# RTCE.net
KiCad netlist of a schematic drawn in Altium Designer
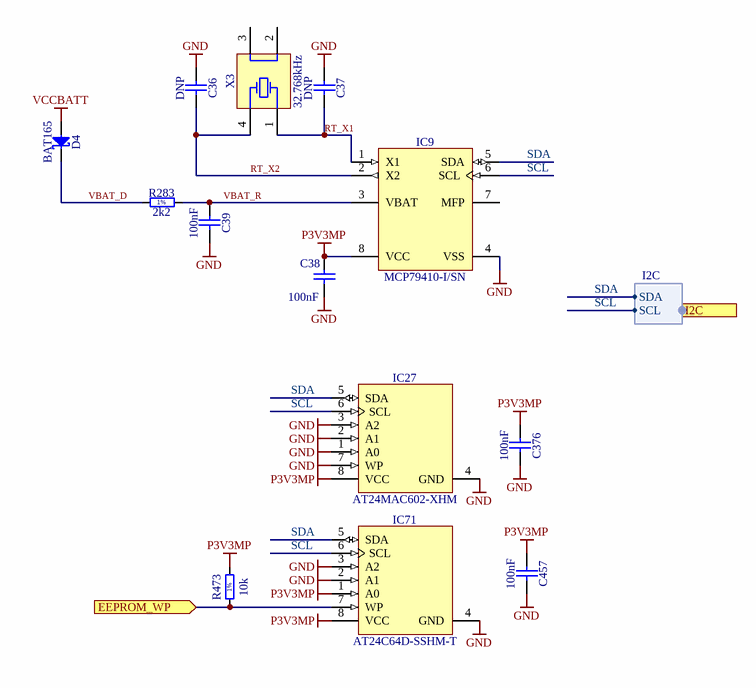
[diagram p0: RTCE.SchDoc]

(export (version "E")
  (design (tool "Eeschema 10.0.6"))
  (components
    (comp (ref "C36")
      (value "DNP")
      (footprint "CAPC1005X55N")
      (description "Non-polarised capacitor")
      (fields
        (field (name "PART NUMBER") "CC0402_15PF_50V_5%_NP0")
        (field (name "VOLTAGE") "50V")
        (field (name "AUTHOR") "CERN DEM JLC")
      )
      (libsource (lib "Capacitors") (part "Capacitor - non polarized"))
    )
    (comp (ref "C37")
      (value "DNP")
      (footprint "CAPC1005X55N")
      (description "Non-polarised capacitor")
      (fields
        (field (name "PART NUMBER") "CC0402_15PF_50V_5%_NP0")
        (field (name "VOLTAGE") "50V")
        (field (name "AUTHOR") "CERN DEM JLC")
      )
      (libsource (lib "Capacitors") (part "Capacitor - non polarized"))
    )
    (comp (ref "C38")
      (value "100nF")
      (footprint "CAPC0603X33N")
      (description "Non-polarised capacitor")
      (fields
        (field (name "PART NUMBER") "CC0201_100NF_6.3V_10%_X5R")
        (field (name "VOLTAGE") "6.3V")
        (field (name "AUTHOR") "CERN DEM JLC")
      )
      (libsource (lib "Capacitors") (part "Capacitor - non polarized"))
    )
    (comp (ref "C39")
      (value "100nF")
      (footprint "CAPC0603X33N")
      (description "Non-polarised capacitor")
      (fields
        (field (name "PART NUMBER") "CC0201_100NF_6.3V_10%_X5R")
        (field (name "VOLTAGE") "6.3V")
        (field (name "AUTHOR") "CERN DEM JLC")
      )
      (libsource (lib "Capacitors") (part "Capacitor - non polarized"))
    )
    (comp (ref "C376")
      (value "100nF")
      (footprint "CAPC0603X33N")
      (description "Non-polarised capacitor")
      (fields
        (field (name "PART NUMBER") "CC0201_100NF_6.3V_10%_X5R")
        (field (name "VOLTAGE") "6.3V")
        (field (name "AUTHOR") "CERN DEM JLC")
      )
      (libsource (lib "Capacitors") (part "Capacitor - non polarized"))
    )
    (comp (ref "C457")
      (value "100nF")
      (footprint "CAPC0603X33N")
      (description "Non-polarised capacitor")
      (fields
        (field (name "PART NUMBER") "CC0201_100NF_6.3V_10%_X5R")
        (field (name "VOLTAGE") "6.3V")
        (field (name "AUTHOR") "CERN DEM JLC")
      )
      (libsource (lib "Capacitors") (part "Capacitor - non polarized"))
    )
    (comp (ref "D4")
      (value "BAT165")
      (footprint "SOD2512X110N")
      (description "Schottky Diode")
      (fields
        (field (name "VOLTAGE") "40V")
        (field (name "POWER") "750mA")
        (field (name "AUTHOR") "CERN DEM JLC")
      )
      (libsource (lib "ICs And Semiconductors") (part "Diode Schottky"))
    )
    (comp (ref "IC9")
      (value "MCP79410-I/SN")
      (footprint "SOIC127P600X175-8N")
      (description "I2C Real-Time Clock/Calendar with EEPROM, SRAM, Unique ID and Battery Switchover")
      (fields (field (name "MANUFACTURER") "MICROCHIP TECHNOLOGY") (field (name "AUTHOR") "CERN DEM JMW"))
      (libsource (lib "ICs And Semiconductors") (part "MCP79410"))
    )
    (comp (ref "IC27")
      (value "AT24MAC602-XHM")
      (footprint "SOP65P640X120-8N")
      (description "1.7V to 5.5V, I2C-Compatible (2-wire) 2-Kbit (256 x 8) Serial EEPROM")
      (fields (field (name "MANUFACTURER") "ATMEL") (field (name "AUTHOR") "CERN DEM MR"))
      (libsource (lib "ICs And Semiconductors") (part "AT24MAC602-XHM"))
    )
    (comp (ref "IC71")
      (value "AT24C64D-SSHM-T")
      (footprint "SOIC127P600X175-8N")
      (description "64K (8192 x 8), I2C-Compatible (2-Wire) Serial EEPROM")
      (fields (field (name "MANUFACTURER") "ATMEL") (field (name "AUTHOR") "CERN DEM JLC"))
      (libsource (lib "ICs And Semiconductors") (part "AT24C64D-SSH"))
    )
    (comp (ref "R283")
      (value "2k2")
      (footprint "RESC1005X40N")
      (description "Resistor - 1%")
      (fields
        (field (name "PART NUMBER") "R0402_2K2_1%_0.0625W_100PPM")
        (field (name "POWER") "0.0625W")
        (field (name "AUTHOR") "CERN DEM JLC")
      )
      (libsource (lib "Resistors") (part "Resistor - 1%"))
    )
    (comp (ref "R473")
      (value "10k")
      (footprint "RESC1005X40N")
      (description "Resistor - 1%")
      (fields
        (field (name "MANUFACTURER PART NUMBER") "R0402_10K_1%_0.0625W_100PPM")
        (field (name "MANUFACTURER") "GENERIC")
        (field (name "AUTHOR") "CERN DEM JLC")
      )
      (libsource (lib "Resistors") (part "Resistor - 1%"))
    )
    (comp (ref "X3")
      (value "32.768kHz")
      (footprint "XTAL_ABRACON_ABS25")
      (description "Crystal 4 pins 1=XTAL Control 2 And 3=NC 4=XTAL")
      (fields
        (field (name "PART NUMBER") "XTAL_32.768KHZ_ABRACON_ABS25-32.768KHZ-T")
        (field (name "MANUFACTURER") "ABRACON")
        (field (name "AUTHOR") "CERN DEM JMW")
      )
      (libsource (lib "ICs And Semiconductors") (part "Quartz Crystal 1X 2-3NC 4X"))
    )
  )
  (nets
    (net (code "2") (name "/EEPROM_WP") (class "Default")
      (node (ref "IC71") (pin "7") (pinfunction "WP_7") (pintype "input"))
      (node (ref "R473") (pin "1") (pinfunction "1_1") (pintype "passive"))
    )
    (net (code "3") (name "/RT_X1") (class "Default")
      (node (ref "C37") (pin "2") (pinfunction "2_2") (pintype "passive"))
      (node (ref "IC9") (pin "1") (pinfunction "X1_1") (pintype "input"))
      (node (ref "X3") (pin "1") (pinfunction "X_1") (pintype "passive"))
    )
    (net (code "4") (name "/RT_X2") (class "Default")
      (node (ref "C36") (pin "2") (pinfunction "2_2") (pintype "passive"))
      (node (ref "IC9") (pin "2") (pinfunction "X2_2") (pintype "output"))
      (node (ref "X3") (pin "4") (pinfunction "X_4") (pintype "passive"))
    )
    (net (code "5") (name "/SCL") (class "Default")
      (node (ref "IC27") (pin "6") (pinfunction "SCL_6") (pintype "input"))
      (node (ref "IC71") (pin "6") (pinfunction "SCL_6") (pintype "input"))
      (node (ref "IC9") (pin "6") (pinfunction "SCL_6") (pintype "input"))
    )
    (net (code "6") (name "/SDA") (class "Default")
      (node (ref "IC27") (pin "5") (pinfunction "SDA_5") (pintype "bidirectional"))
      (node (ref "IC71") (pin "5") (pinfunction "SDA_5") (pintype "bidirectional"))
      (node (ref "IC9") (pin "5") (pinfunction "SDA_5") (pintype "bidirectional"))
    )
    (net (code "7") (name "/VBAT_D") (class "Default")
      (node (ref "D4") (pin "1") (pinfunction "C_1") (pintype "passive"))
      (node (ref "R283") (pin "1") (pinfunction "1_1") (pintype "passive"))
    )
    (net (code "8") (name "/VBAT_R") (class "Default")
      (node (ref "C39") (pin "1") (pinfunction "1_1") (pintype "passive"))
      (node (ref "IC9") (pin "3") (pinfunction "VBAT_3") (pintype "power_in"))
      (node (ref "R283") (pin "2") (pinfunction "2_2") (pintype "passive"))
    )
    (net (code "10") (name "GND") (class "Default")
      (node (ref "C36") (pin "1") (pinfunction "1_1") (pintype "passive"))
      (node (ref "C37") (pin "1") (pinfunction "1_1") (pintype "passive"))
      (node (ref "C376") (pin "2") (pinfunction "2_2") (pintype "passive"))
      (node (ref "C38") (pin "2") (pinfunction "2_2") (pintype "passive"))
      (node (ref "C39") (pin "2") (pinfunction "2_2") (pintype "passive"))
      (node (ref "C457") (pin "2") (pinfunction "2_2") (pintype "passive"))
      (node (ref "IC27") (pin "1") (pinfunction "A0_1") (pintype "input"))
      (node (ref "IC27") (pin "2") (pinfunction "A1_2") (pintype "input"))
      (node (ref "IC27") (pin "3") (pinfunction "A2_3") (pintype "input"))
      (node (ref "IC27") (pin "4") (pinfunction "GND_4") (pintype "power_in"))
      (node (ref "IC27") (pin "7") (pinfunction "WP_7") (pintype "input"))
      (node (ref "IC71") (pin "2") (pinfunction "A1_2") (pintype "input"))
      (node (ref "IC71") (pin "3") (pinfunction "A2_3") (pintype "input"))
      (node (ref "IC71") (pin "4") (pinfunction "GND_4") (pintype "power_in"))
      (node (ref "IC9") (pin "4") (pinfunction "VSS_4") (pintype "power_in"))
    )
    (net (code "11") (name "P3V3MP") (class "Default")
      (node (ref "C376") (pin "1") (pinfunction "1_1") (pintype "passive"))
      (node (ref "C38") (pin "1") (pinfunction "1_1") (pintype "passive"))
      (node (ref "C457") (pin "1") (pinfunction "1_1") (pintype "passive"))
      (node (ref "IC27") (pin "8") (pinfunction "VCC_8") (pintype "power_in"))
      (node (ref "IC71") (pin "1") (pinfunction "A0_1") (pintype "input"))
      (node (ref "IC71") (pin "8") (pinfunction "VCC_8") (pintype "power_in"))
      (node (ref "IC9") (pin "8") (pinfunction "VCC_8") (pintype "power_in"))
      (node (ref "R473") (pin "2") (pinfunction "2_2") (pintype "passive"))
    )
    (net (code "12") (name "VCCBATT") (class "Default")
      (node (ref "D4") (pin "2") (pinfunction "A_2") (pintype "passive"))
    )
    (net (code "13") (name "unconnected-(IC9-MFP-Pad7)") (class "Default")
      (node (ref "IC9") (pin "7") (pinfunction "MFP_7") (pintype "open_collector"))
    )
    (net (code "14") (name "unconnected-(X3-GND-Pad2)") (class "Default")
      (node (ref "X3") (pin "2") (pinfunction "GND_2") (pintype "power_in"))
    )
    (net (code "15") (name "unconnected-(X3-GND-Pad3)") (class "Default")
      (node (ref "X3") (pin "3") (pinfunction "GND_3") (pintype "power_in"))
    )
  )
)
